# REUN_468349_001_PSU_Board_3V3_Logic.net
KiCad netlist of a schematic drawn in Altium Designer
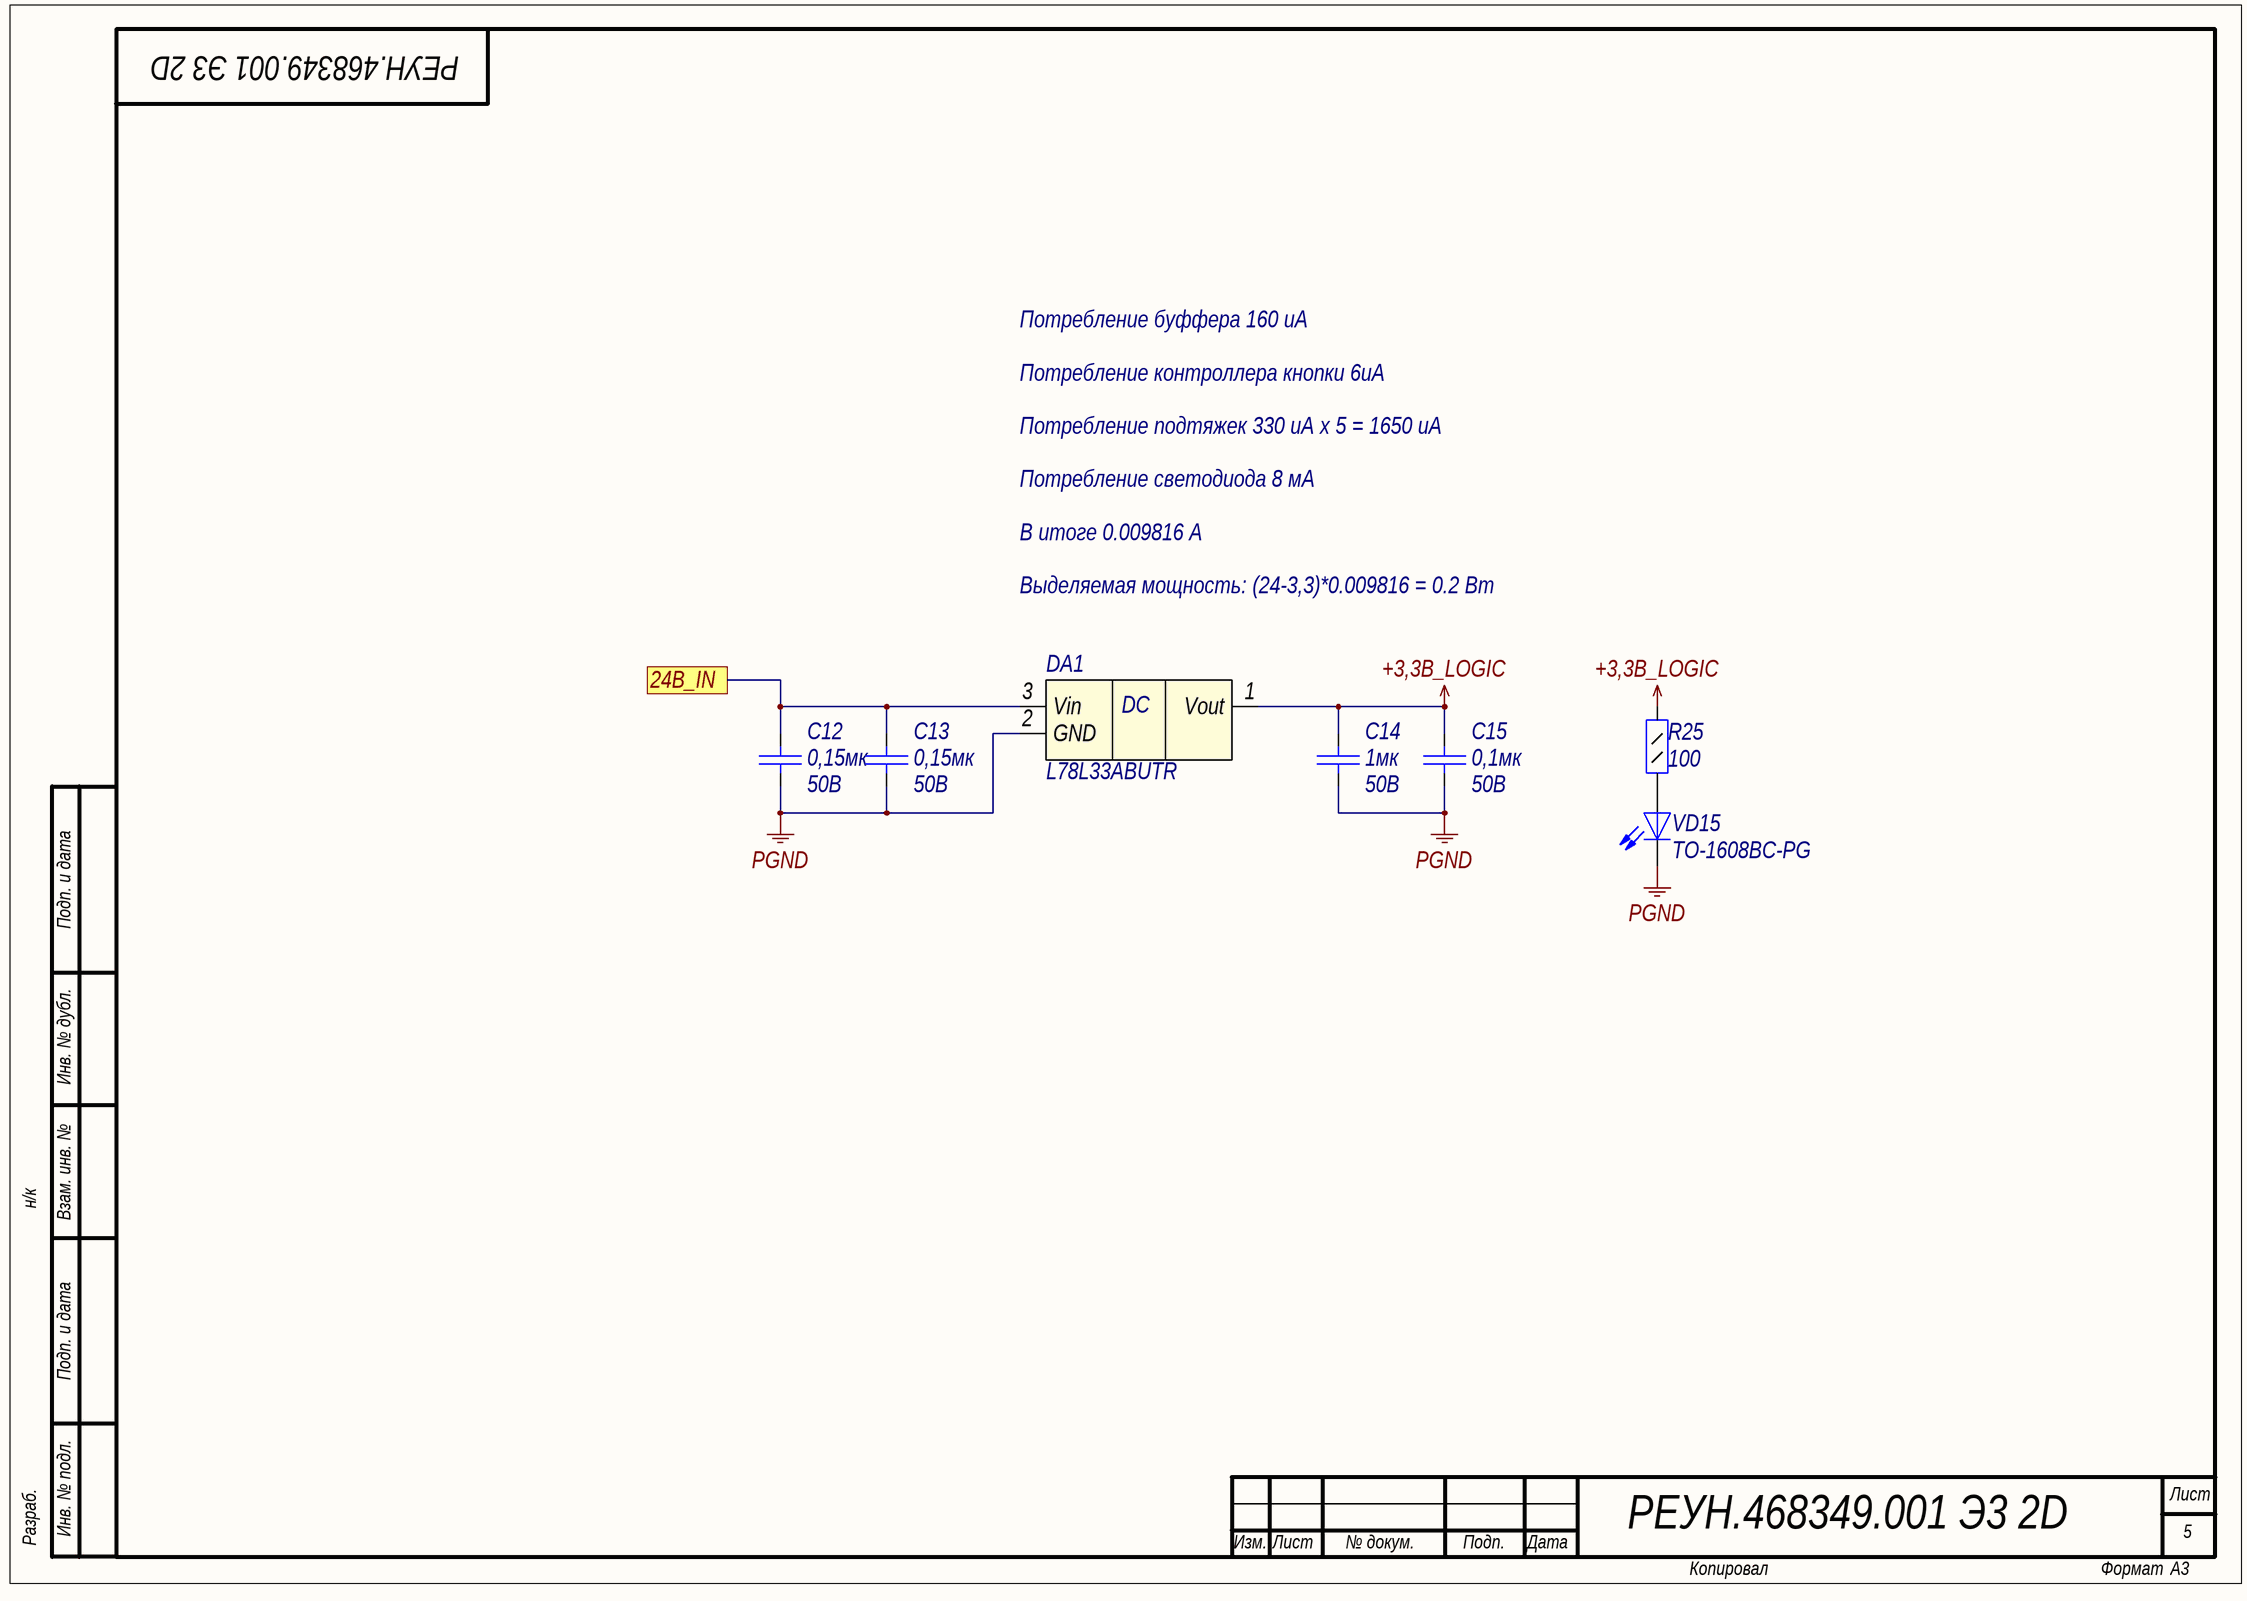
[diagram p0: REUN.468349.001_PSU_Board_3V3_Logic.SchDoc]

(export (version "E")
  (design (tool "Eeschema 10.0.6"))
  (components
    (comp (ref "C12")
      (value "0,15мк")
      (footprint "C0805")
      (description "Конденсатор")
      (fields (field (name "VOLTAGE") "50B") (field (name "PART NUMBER") "GRM21BR71H154K"))
      (libsource (lib "MOP44") (part "Capacitor"))
    )
    (comp (ref "C13")
      (value "0,15мк")
      (footprint "C0805")
      (description "Конденсатор")
      (fields (field (name "VOLTAGE") "50B") (field (name "PART NUMBER") "GRM21BR71H154K"))
      (libsource (lib "MOP44") (part "Capacitor"))
    )
    (comp (ref "C14")
      (value "1мк")
      (footprint "C0805")
      (description "Конденсатор")
      (fields (field (name "VOLTAGE") "50B") (field (name "PART NUMBER") "GRM21BR71H105KA12L"))
      (libsource (lib "MOP44") (part "Capacitor"))
    )
    (comp (ref "C15")
      (value "0,1мк")
      (footprint "C0805")
      (description "Конденсатор")
      (fields (field (name "VOLTAGE") "50B") (field (name "PART NUMBER") "GRM21BR71H104KA01K"))
      (libsource (lib "MOP44") (part "Capacitor"))
    )
    (comp (ref "DA1")
      (value "L78L33ABUTR")
      (footprint "SOT-89-3")
      (description "Cтабилизатор напряжения (+3,3В; 0.1А), 4%, (-40...+125C)")
      (fields (field (name "MANUFACTURER") "ST Microelectronics"))
      (libsource (lib "MOP44") (part "L78LxxABUTR"))
    )
    (comp (ref "R25")
      (value "100")
      (footprint "R0805")
      (description "Резистор")
      (fields (field (name "PART NUMBER") "RC0805FR-07100RL") (field (name "POWER") "0,125Вт"))
      (libsource (lib "MOP44") (part "Resistor_0,125Вт"))
    )
    (comp (ref "VD15")
      (value "TO-1608BC-PG")
      (footprint "L_0603_GREEN")
      (description "Светодиод")
      (libsource (lib "MOP44") (part "LED"))
    )
  )
  (nets
    (net (code "1") (name "+3,3B_LOGIC") (class "Default")
      (node (ref "C14") (pin "2") (pinfunction "2_2") (pintype "passive"))
      (node (ref "C15") (pin "2") (pinfunction "2_2") (pintype "passive"))
      (node (ref "DA1") (pin "1") (pinfunction "Vout_1") (pintype "power_in"))
      (node (ref "R25") (pin "2") (pinfunction "2_2") (pintype "passive"))
    )
    (net (code "2") (name "/24B_IN") (class "Default")
      (node (ref "C12") (pin "1") (pinfunction "1_1") (pintype "passive"))
      (node (ref "C13") (pin "1") (pinfunction "1_1") (pintype "passive"))
      (node (ref "DA1") (pin "3") (pinfunction "Vin_3") (pintype "power_in"))
    )
    (net (code "3") (name "Net-(VD15-A)") (class "Default")
      (node (ref "R25") (pin "1") (pinfunction "1_1") (pintype "passive"))
      (node (ref "VD15") (pin "2") (pinfunction "A_2") (pintype "passive"))
    )
    (net (code "4") (name "PGND") (class "Default")
      (node (ref "C12") (pin "2") (pinfunction "2_2") (pintype "passive"))
      (node (ref "C13") (pin "2") (pinfunction "2_2") (pintype "passive"))
      (node (ref "C14") (pin "1") (pinfunction "1_1") (pintype "passive"))
      (node (ref "C15") (pin "1") (pinfunction "1_1") (pintype "passive"))
      (node (ref "DA1") (pin "2") (pinfunction "GND_2") (pintype "power_in"))
      (node (ref "VD15") (pin "1") (pinfunction "K_1") (pintype "passive"))
    )
  )
)
